# zp_zh.net
KiCad netlist of a schematic drawn in Altium Designer
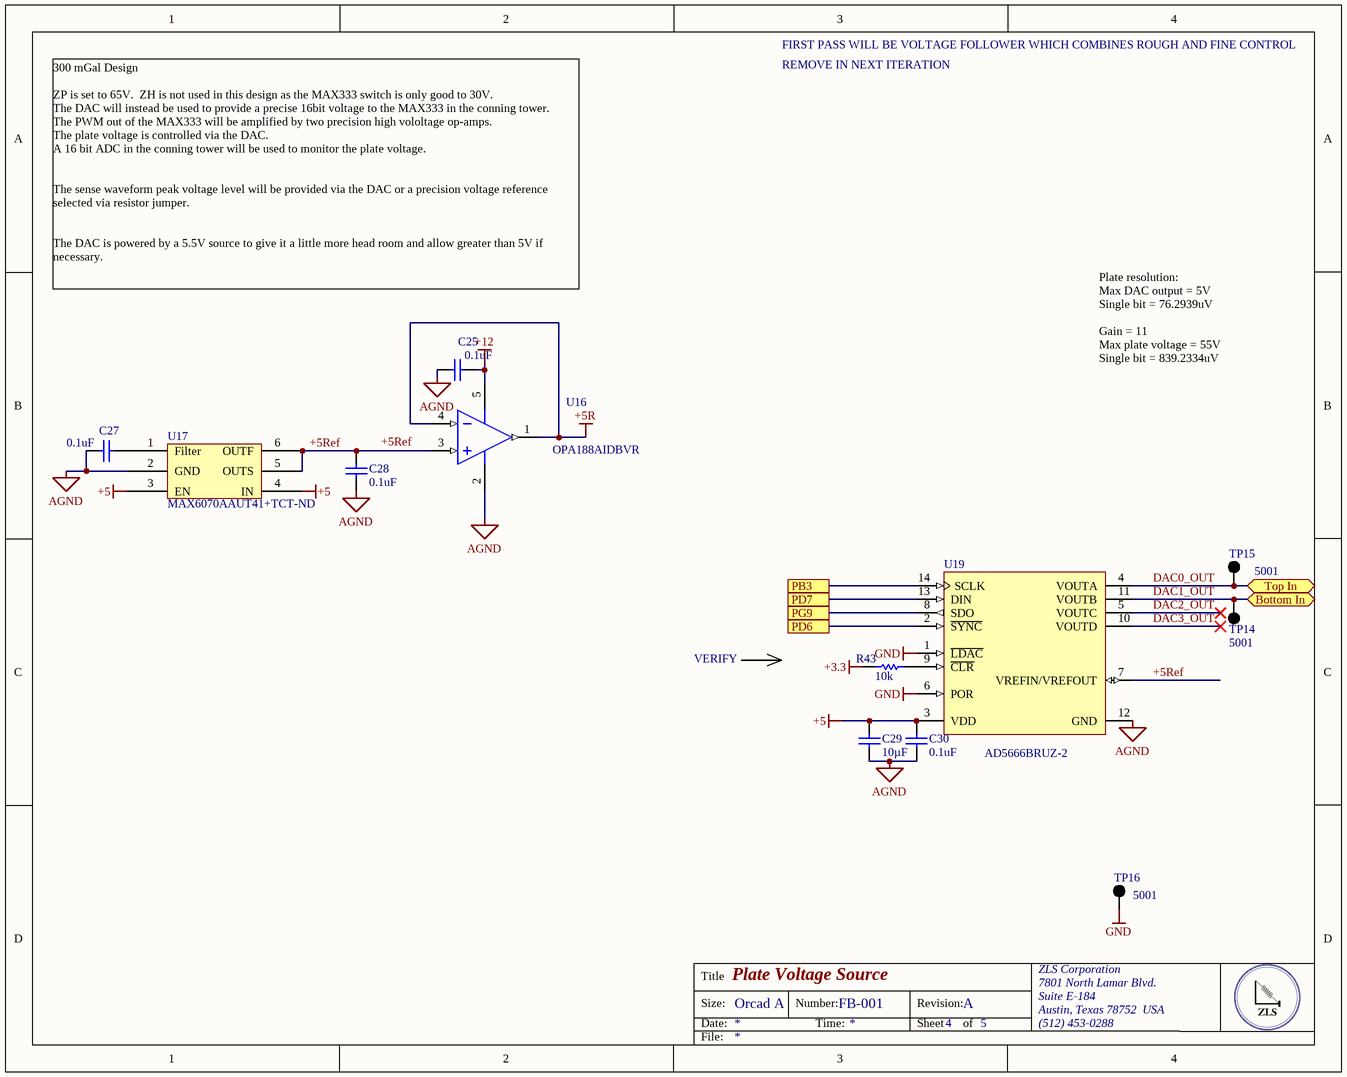
[diagram p0: zp_zh.SchDoc]

(export (version "E")
  (design (tool "Eeschema 10.0.6"))
  (components
    (comp (ref "C25")
      (value "0.1uF")
      (footprint "CAPC0402(1005)60_L")
      (description "CAP CER 0.1UF 10V X7R 0402")
      (fields
        (field (name "MANUFACTURER") "Murata Electronics North America")
        (field (name "MANUFACTURER PART NUMBER") "GRM155R71A104KA01D")
      )
      (libsource (lib "Altium Content Vault") (part "CMP-1034-00252-1"))
    )
    (comp (ref "C27")
      (value "0.1uF")
      (footprint "CAPC0402(1005)60_L")
      (description "CAP CER 0.1UF 10V X7R 0402")
      (fields
        (field (name "MANUFACTURER") "Murata Electronics North America")
        (field (name "MANUFACTURER PART NUMBER") "GRM155R71A104KA01D")
      )
      (libsource (lib "Altium Content Vault") (part "CMP-1034-00252-1"))
    )
    (comp (ref "C28")
      (value "0.1uF")
      (footprint "CAPC0402(1005)60_L")
      (description "CAP CER 0.1UF 10V X7R 0402")
      (fields
        (field (name "MANUFACTURER") "Murata Electronics North America")
        (field (name "MANUFACTURER PART NUMBER") "GRM155R71A104KA01D")
      )
      (libsource (lib "Altium Content Vault") (part "CMP-1034-00252-1"))
    )
    (comp (ref "C29")
      (value "10uF")
      (footprint "CAPC0805(2012)145_N")
      (description "CAP CER 10UF 25V X7R 0805")
      (fields
        (field (name "MANUFACTURER") "Murata Electronics North America")
        (field (name "MANUFACTURER PART NUMBER") "GRM21BR71E104KA01L")
        (field (name "CAPACITANCE") "10µF")
      )
      (libsource (lib "Altium Content Vault") (part "CMP-1036-04795-1"))
    )
    (comp (ref "C30")
      (value "0.1uF")
      (footprint "CAPC0402(1005)60_L")
      (description "CAP CER 0.1UF 10V X7R 0402")
      (fields
        (field (name "MANUFACTURER") "Murata Electronics North America")
        (field (name "MANUFACTURER PART NUMBER") "GRM155R71A104KA01D")
      )
      (libsource (lib "Altium Content Vault") (part "CMP-1034-00252-1"))
    )
    (comp (ref "R43")
      (value "10k")
      (footprint "RESC0402(1005)_M")
      (description "10k 0.063W 1% 0402 (1005 Metric)  SMD")
      (fields
        (field (name "MANUFACTURER") "Panasonic")
        (field (name "MANUFACTURER PART NUMBER") "ERJ-2RKF1002X")
      )
      (libsource (lib "Altium Content Vault") (part "RES"))
    )
    (comp (ref "TP14")
      (value "5001")
      (footprint "KSTN-5001")
      (description "Test Point, Black, 1-Pin THD, RoHS, Bulk")
      (fields (field (name "MANUFACTURER") "Keystone"))
      (libsource (lib "Altium Content Vault") (part "KSTN-TP-5001"))
    )
    (comp (ref "TP15")
      (value "5001")
      (footprint "KSTN-5001")
      (description "Test Point, Black, 1-Pin THD, RoHS, Bulk")
      (fields (field (name "MANUFACTURER") "Keystone"))
      (libsource (lib "Altium Content Vault") (part "KSTN-TP-5001"))
    )
    (comp (ref "TP16")
      (value "5001")
      (footprint "KSTN-5001")
      (description "Test Point, Black, 1-Pin THD, RoHS, Bulk")
      (fields (field (name "MANUFACTURER") "Keystone"))
      (libsource (lib "Altium Content Vault") (part "KSTN-TP-5001"))
    )
    (comp (ref "U16")
      (value "OPA188AIDBVR")
      (footprint "DBV0005A_M")
      (fields (field (name "MANUFACTURER") "Texas Instruments"))
      (libsource (lib "Altium Content Vault") (part "CMP-0809-00005-2"))
    )
    (comp (ref "U17")
      (value "MAX6070AAUT41+T")
      (footprint "SOT95P280X445-6N")
      (description "IC VREF SERIES 4.096V SOT23")
      (fields
        (field (name "SUPPLIER PART NUMBER 1") "MAX6070AAUT41+TCT-ND")
        (field (name "MANUFACTURER") "Maxim Integrated")
        (field (name "TOLERANCE") "±0.04%")
      )
      (libsource (lib "ZLS_Schematic_lib") (part "MAX6070AAUT41+T"))
    )
    (comp (ref "U19")
      (value "AD5666BRUZ-2")
      (footprint "RU-14_N")
      (fields (field (name "GENERIC PART NUMBER") "AD5666") (field (name "MANUFACTURER") "Analog Devices"))
      (libsource (lib "Altium Content Vault") (part "ADI-AD5666-RU-14"))
    )
  )
  (nets
    (net (code "1") (name "+3.3") (class "Default")
      (node (ref "R43") (pin "1") (pinfunction "1_1") (pintype "passive"))
    )
    (net (code "2") (name "+5") (class "Default")
      (node (ref "C29") (pin "2") (pinfunction "2_2") (pintype "passive"))
      (node (ref "C30") (pin "1") (pinfunction "1_1") (pintype "passive"))
      (node (ref "U17") (pin "3") (pinfunction "EN_3") (pintype "passive"))
      (node (ref "U17") (pin "4") (pinfunction "IN_4") (pintype "passive"))
      (node (ref "U19") (pin "3") (pinfunction "VDD_3") (pintype "power_in"))
    )
    (net (code "3") (name "+5R") (class "Default")
      (node (ref "U16") (pin "1") (pinfunction "OUT_1") (pintype "output"))
      (node (ref "U16") (pin "4") (pinfunction "IN-_4") (pintype "input"))
    )
    (net (code "4") (name "+12") (class "Default")
      (node (ref "C25") (pin "1") (pinfunction "1_1") (pintype "passive"))
      (node (ref "U16") (pin "5") (pinfunction "V+_5") (pintype "power_in"))
    )
    (net (code "5") (name "/+5Ref") (class "Default")
      (node (ref "C28") (pin "2") (pinfunction "2_2") (pintype "passive"))
      (node (ref "U16") (pin "3") (pinfunction "IN+_3") (pintype "input"))
      (node (ref "U17") (pin "5") (pinfunction "OUTS_5") (pintype "passive"))
      (node (ref "U17") (pin "6") (pinfunction "OUTF_6") (pintype "passive"))
      (node (ref "U19") (pin "7") (pinfunction "VREFIN/VREFOUT_7") (pintype "bidirectional"))
    )
    (net (code "6") (name "/DAC0_OUT") (class "Default")
      (node (ref "TP15") (pin "1") (pintype "passive"))
      (node (ref "U19") (pin "4") (pinfunction "VOUTA_4") (pintype "tri_state"))
    )
    (net (code "7") (name "/DAC1_OUT") (class "Default")
      (node (ref "TP14") (pin "1") (pintype "passive"))
      (node (ref "U19") (pin "11") (pinfunction "VOUTB_11") (pintype "tri_state"))
    )
    (net (code "8") (name "/DAC2_OUT") (class "Default")
      (node (ref "U19") (pin "5") (pinfunction "VOUTC_5") (pintype "tri_state+no_connect"))
    )
    (net (code "9") (name "/DAC3_OUT") (class "Default")
      (node (ref "U19") (pin "10") (pinfunction "VOUTD_10") (pintype "tri_state+no_connect"))
    )
    (net (code "10") (name "/PB3") (class "Default")
      (node (ref "U19") (pin "14") (pinfunction "SCLK_14") (pintype "input"))
    )
    (net (code "11") (name "/PD6") (class "Default")
      (node (ref "U19") (pin "2") (pinfunction "~{SYNC}_2") (pintype "input"))
    )
    (net (code "12") (name "/PD7") (class "Default")
      (node (ref "U19") (pin "13") (pinfunction "DIN_13") (pintype "input"))
    )
    (net (code "13") (name "/PG9") (class "Default")
      (node (ref "U19") (pin "8") (pinfunction "SDO_8") (pintype "output"))
    )
    (net (code "14") (name "AGND") (class "Default")
      (node (ref "C25") (pin "2") (pinfunction "2_2") (pintype "passive"))
      (node (ref "C27") (pin "2") (pinfunction "2_2") (pintype "passive"))
      (node (ref "C28") (pin "1") (pinfunction "1_1") (pintype "passive"))
      (node (ref "C29") (pin "1") (pinfunction "1_1") (pintype "passive"))
      (node (ref "C30") (pin "2") (pinfunction "2_2") (pintype "passive"))
      (node (ref "U16") (pin "2") (pinfunction "V-_2") (pintype "power_in"))
      (node (ref "U17") (pin "2") (pinfunction "GND_2") (pintype "passive"))
      (node (ref "U19") (pin "12") (pinfunction "GND_12") (pintype "power_in"))
    )
    (net (code "15") (name "GND") (class "Default")
      (node (ref "TP16") (pin "1") (pintype "passive"))
      (node (ref "U19") (pin "1") (pinfunction "~{LDAC}_1") (pintype "input"))
      (node (ref "U19") (pin "6") (pinfunction "POR_6") (pintype "input"))
    )
    (net (code "16") (name "Net-(U17-Filter)") (class "Default")
      (node (ref "C27") (pin "1") (pinfunction "1_1") (pintype "passive"))
      (node (ref "U17") (pin "1") (pinfunction "Filter_1") (pintype "passive"))
    )
    (net (code "17") (name "Net-(U19-~{CLR})") (class "Default")
      (node (ref "R43") (pin "2") (pinfunction "2_2") (pintype "passive"))
      (node (ref "U19") (pin "9") (pinfunction "~{CLR}_9") (pintype "input"))
    )
  )
)
